# Display_Board_v4.net
KiCad netlist of a schematic drawn in EAGLE
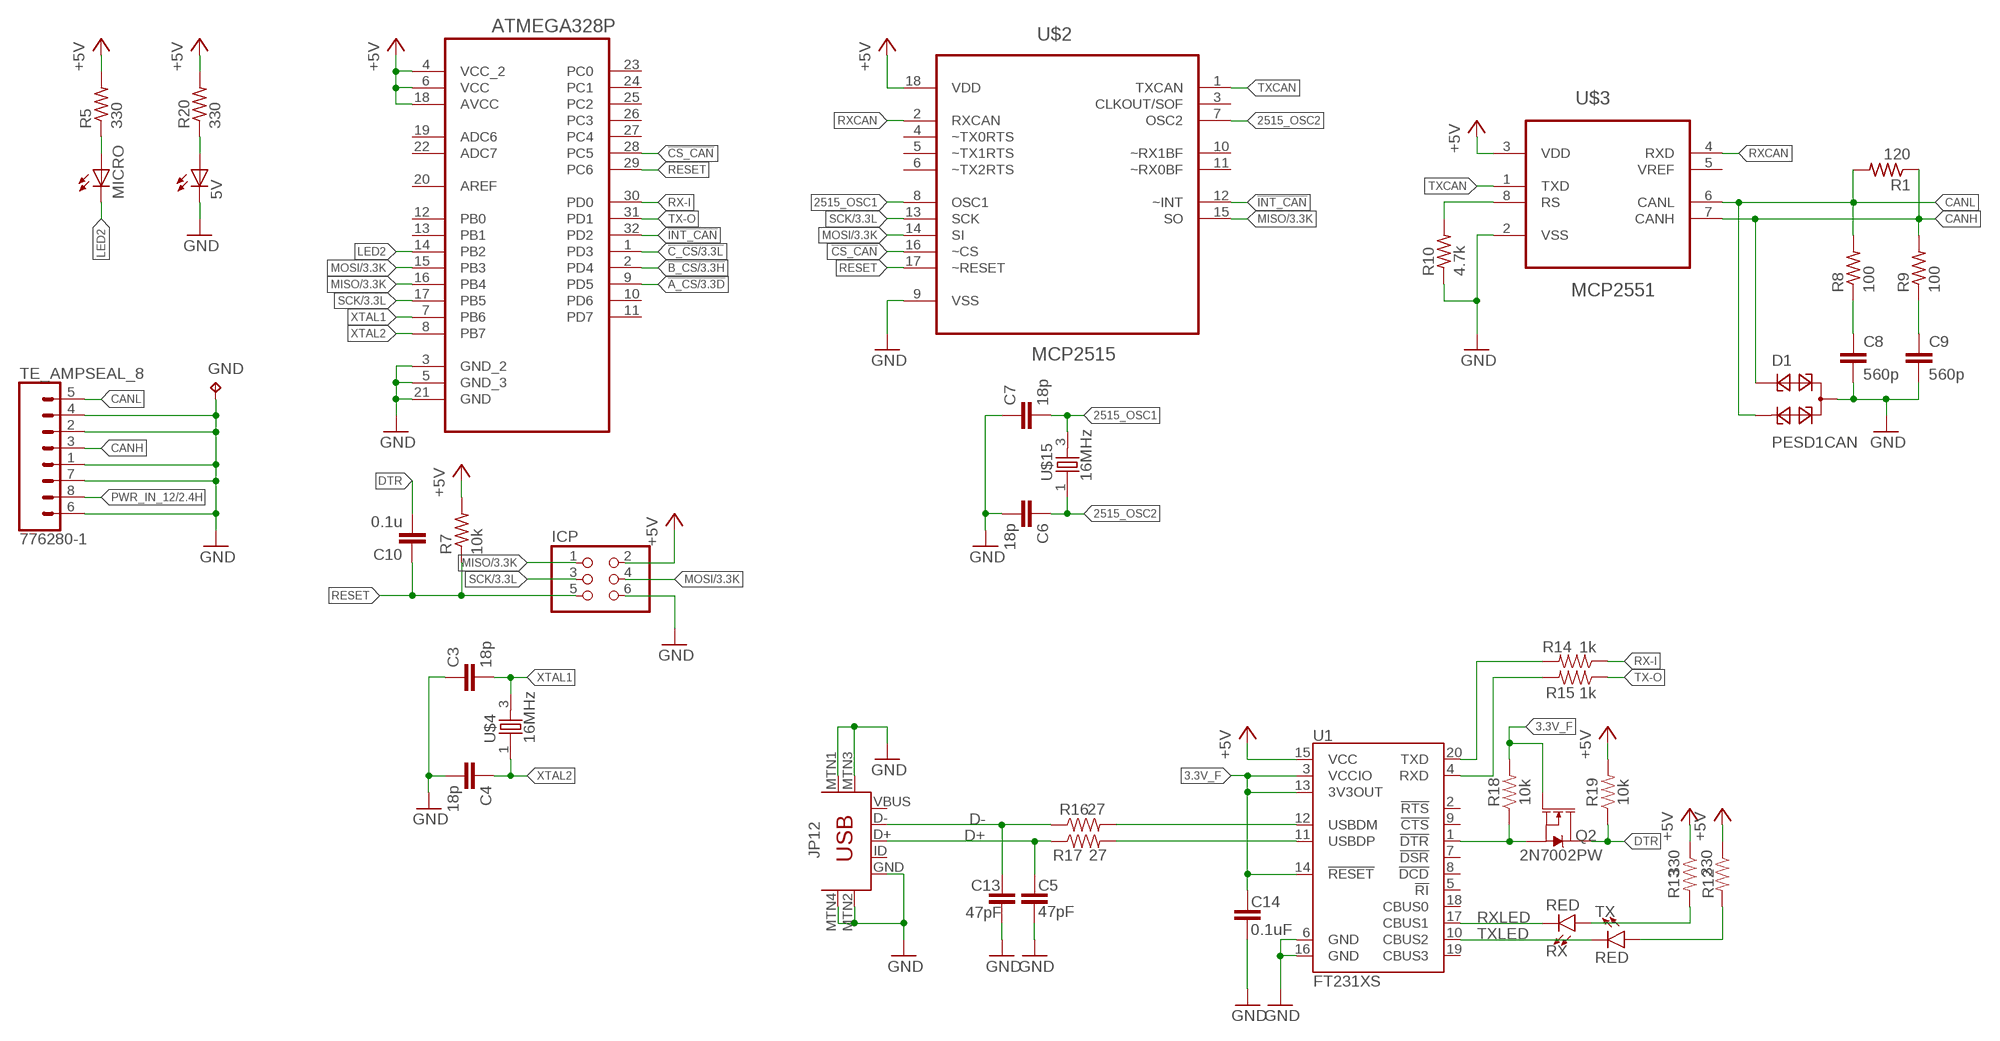
[diagram p0: schematic, sheet 1]
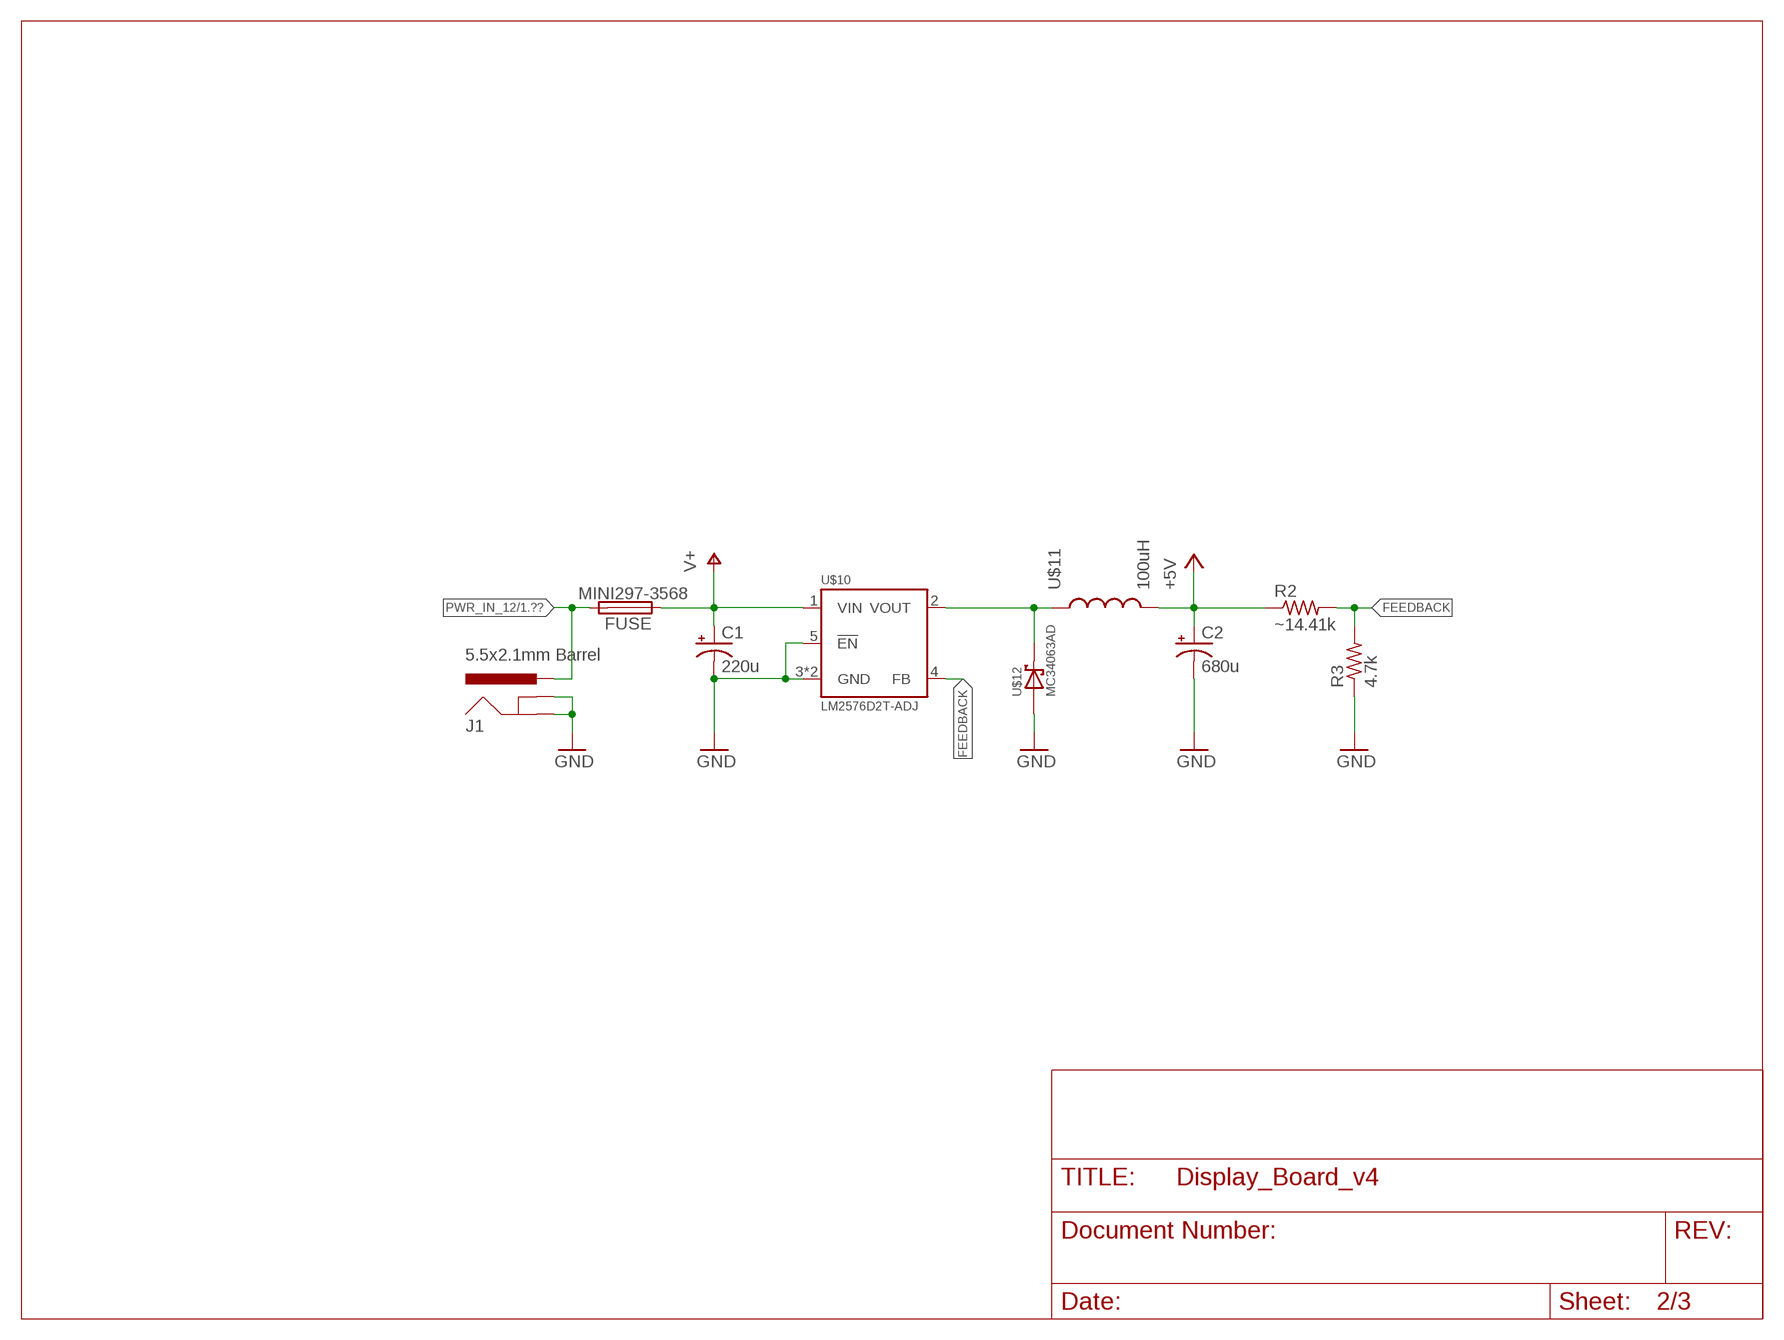
[diagram p1: schematic, sheet 2]
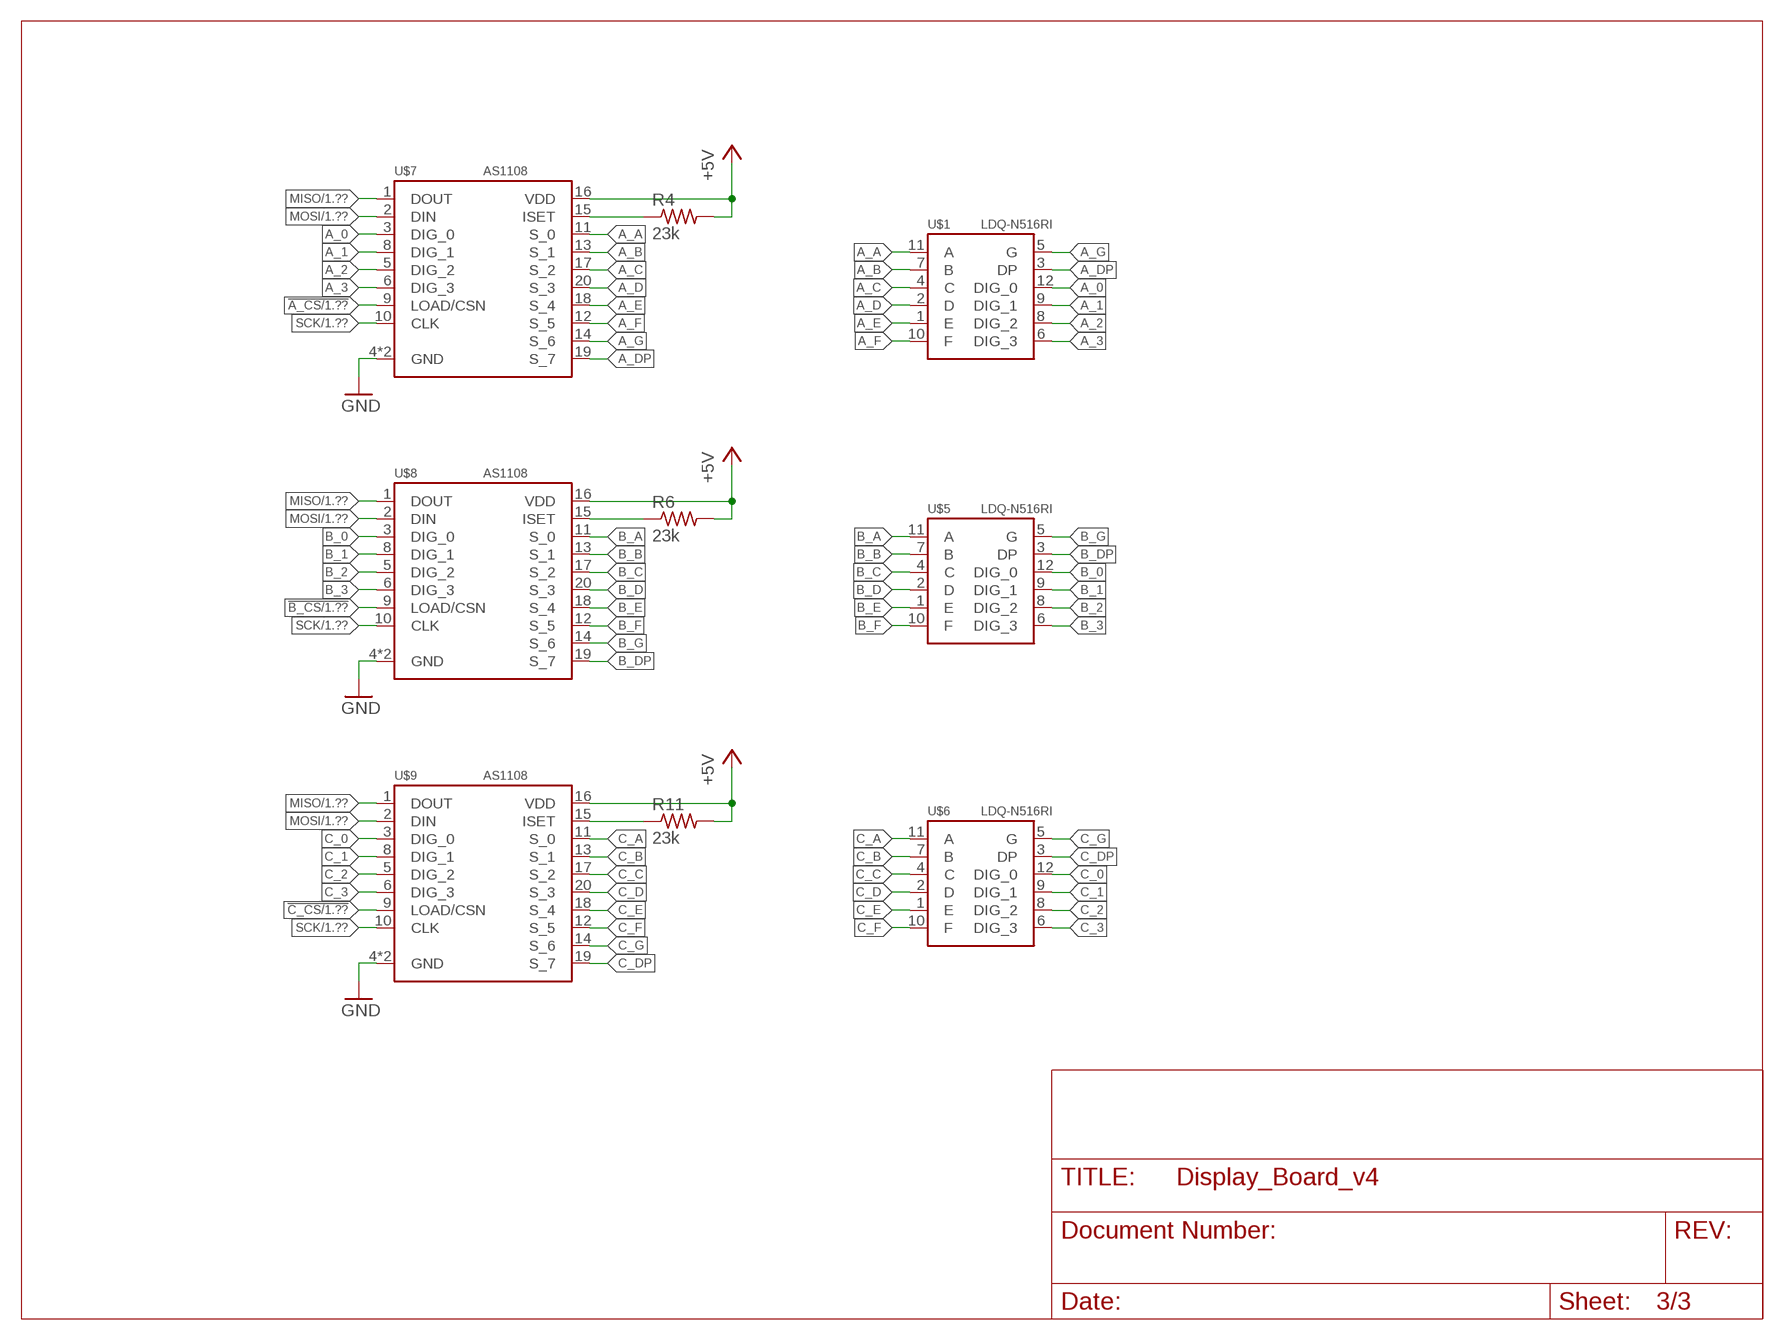
[diagram p2: schematic, sheet 3]

(export (version "E")
  (design (tool "Eeschema 10.0.6"))
  (components
    (comp (ref "5V")
      (value "LEDCHIP-LED0805")
      (footprint "eagle-import:CHIP-LED0805")
      (libsource (lib "eagle-import") (part "LEDCHIP-LED0805"))
    )
    (comp (ref "ATMEGA328P")
      (value "ATMEGA328P-AU")
      (footprint "eagle-import:QFP80P900X900X120-32N")
      (libsource (lib "eagle-import") (part "ATMEGA328P-AU"))
    )
    (comp (ref "C3")
      (value "18p")
      (footprint "eagle-import:C0805K")
      (libsource (lib "eagle-import") (part "resistor_C-EUC0805K"))
    )
    (comp (ref "C4")
      (value "18p")
      (footprint "eagle-import:C0805K")
      (libsource (lib "eagle-import") (part "resistor_C-EUC0805K"))
    )
    (comp (ref "C5")
      (value "47pF")
      (footprint "eagle-import:0603")
      (libsource (lib "eagle-import") (part "47PF-0603-50V-5%"))
    )
    (comp (ref "C6")
      (value "18p")
      (footprint "eagle-import:C0805K")
      (libsource (lib "eagle-import") (part "resistor_C-EUC0805K"))
    )
    (comp (ref "C7")
      (value "18p")
      (footprint "eagle-import:C0805K")
      (libsource (lib "eagle-import") (part "resistor_C-EUC0805K"))
    )
    (comp (ref "C8")
      (value "560p")
      (footprint "eagle-import:C0805K")
      (libsource (lib "eagle-import") (part "C-EUC0805K"))
    )
    (comp (ref "C9")
      (value "560p")
      (footprint "eagle-import:C0805K")
      (libsource (lib "eagle-import") (part "C-EUC0805K"))
    )
    (comp (ref "C10")
      (value "0.1u")
      (footprint "eagle-import:C0805K")
      (libsource (lib "eagle-import") (part "resistor_C-EUC0805K"))
    )
    (comp (ref "C13")
      (value "47pF")
      (footprint "eagle-import:0603")
      (libsource (lib "eagle-import") (part "47PF-0603-50V-5%"))
    )
    (comp (ref "C14")
      (value "0.1uF")
      (footprint "eagle-import:0603")
      (libsource (lib "eagle-import") (part "0.1UF-0603-25V-(+80/-20%)"))
    )
    (comp (ref "D1")
      (value "PESD1CAN")
      (footprint "eagle-import:SOT23")
      (libsource (lib "eagle-import") (part "PESD1CAN"))
    )
    (comp (ref "GND")
      (value "TPTP12SQ")
      (footprint "eagle-import:TP12SQ")
      (libsource (lib "eagle-import") (part "TPTP12SQ"))
    )
    (comp (ref "ICP")
      (value "PINHD-2X3")
      (footprint "eagle-import:2X03")
      (libsource (lib "eagle-import") (part "PINHD-2X3"))
    )
    (comp (ref "JP12")
      (value "USB-MINIB-5PIN")
      (footprint "eagle-import:USB-MINIB")
      (libsource (lib "eagle-import") (part "USB-MINIB-5PIN"))
    )
    (comp (ref "MICRO")
      (value "LEDCHIP-LED0805")
      (footprint "eagle-import:CHIP-LED0805")
      (libsource (lib "eagle-import") (part "LEDCHIP-LED0805"))
    )
    (comp (ref "Q2")
      (value "2N7002PW")
      (footprint "eagle-import:SOT323")
      (libsource (lib "eagle-import") (part "MOSFET-NCH-2N7002PW"))
    )
    (comp (ref "R1")
      (value "120")
      (footprint "eagle-import:R0805")
      (libsource (lib "eagle-import") (part "R-US_R0805"))
    )
    (comp (ref "R5")
      (value "330")
      (footprint "eagle-import:R0805")
      (libsource (lib "eagle-import") (part "resistor_R-US_R0805"))
    )
    (comp (ref "R7")
      (value "10k")
      (footprint "eagle-import:R0805")
      (libsource (lib "eagle-import") (part "R-US_R0805"))
    )
    (comp (ref "R8")
      (value "100")
      (footprint "eagle-import:R0805")
      (libsource (lib "eagle-import") (part "R-US_R0805"))
    )
    (comp (ref "R9")
      (value "100")
      (footprint "eagle-import:R0805")
      (libsource (lib "eagle-import") (part "R-US_R0805"))
    )
    (comp (ref "R10")
      (value "4.7k")
      (footprint "eagle-import:R0805")
      (libsource (lib "eagle-import") (part "R-US_R0805"))
    )
    (comp (ref "R12")
      (value "330")
      (footprint "eagle-import:0603")
      (libsource (lib "eagle-import") (part "1KOHM-0603-1/10W-1%"))
    )
    (comp (ref "R13")
      (value "330")
      (footprint "eagle-import:0603")
      (libsource (lib "eagle-import") (part "1KOHM-0603-1/10W-1%"))
    )
    (comp (ref "R14")
      (value "1k")
      (footprint "eagle-import:0603")
      (libsource (lib "eagle-import") (part "1KOHM-0603-1/10W-1%"))
    )
    (comp (ref "R15")
      (value "1k")
      (footprint "eagle-import:0603")
      (libsource (lib "eagle-import") (part "1KOHM-0603-1/10W-1%"))
    )
    (comp (ref "R16")
      (value "27")
      (footprint "eagle-import:0603")
      (libsource (lib "eagle-import") (part "27OHM-0603-1/10W-1%"))
    )
    (comp (ref "R17")
      (value "27")
      (footprint "eagle-import:0603")
      (libsource (lib "eagle-import") (part "27OHM-0603-1/10W-1%"))
    )
    (comp (ref "R18")
      (value "10k")
      (footprint "eagle-import:0603")
      (libsource (lib "eagle-import") (part "10KOHM-0603-1/10W-1%"))
    )
    (comp (ref "R19")
      (value "10k")
      (footprint "eagle-import:0603")
      (libsource (lib "eagle-import") (part "10KOHM-0603-1/10W-1%"))
    )
    (comp (ref "R20")
      (value "330")
      (footprint "eagle-import:R0805")
      (libsource (lib "eagle-import") (part "resistor_R-US_R0805"))
    )
    (comp (ref "RX")
      (value "RED")
      (footprint "eagle-import:LED-1206")
      (libsource (lib "eagle-import") (part "LED1206"))
    )
    (comp (ref "TE_AMPSEAL_8")
      (value "776280-1")
      (footprint "eagle-import:776280-1")
      (libsource (lib "eagle-import") (part "776280-1"))
    )
    (comp (ref "TX")
      (value "RED")
      (footprint "eagle-import:LED-1206")
      (libsource (lib "eagle-import") (part "LED1206"))
    )
    (comp (ref "U$2")
      (value "MCP2515")
      (footprint "eagle-import:SOIC127P1034X264-18N")
      (fields (field (name "MPN") "MCP2515-I/SO"))
      (libsource (lib "eagle-import") (part "MCP2515-I/SO"))
    )
    (comp (ref "U$3")
      (value "MCP2551")
      (footprint "eagle-import:SOIC127P600X175-8N")
      (fields (field (name "MPN") "MCP2551-I/SN"))
      (libsource (lib "eagle-import") (part "MCP2551-I/SN"))
    )
    (comp (ref "U$4")
      (value "16MHz")
      (footprint "eagle-import:CTS406")
      (libsource (lib "eagle-import") (part "406CYRYSTAL"))
    )
    (comp (ref "U$15")
      (value "16MHz")
      (footprint "eagle-import:CTS406")
      (libsource (lib "eagle-import") (part "406CYRYSTAL"))
    )
    (comp (ref "U1")
      (value "FT231XS")
      (footprint "eagle-import:SSOP20_L")
      (libsource (lib "eagle-import") (part "FT231XS"))
    )
    (comp (ref "R4")
      (value "23k")
      (footprint "eagle-import:R0603")
      (libsource (lib "eagle-import") (part "rcl_334_R-US_R0603"))
    )
    (comp (ref "R6")
      (value "23k")
      (footprint "eagle-import:R0603")
      (libsource (lib "eagle-import") (part "rcl_334_R-US_R0603"))
    )
    (comp (ref "R11")
      (value "23k")
      (footprint "eagle-import:R0603")
      (libsource (lib "eagle-import") (part "rcl_334_R-US_R0603"))
    )
    (comp (ref "U$1")
      (value "LDQ-N516RI")
      (footprint "eagle-import:4_DIGIT_7_SEGMENT_DISPLAY_0.56_")
      (libsource (lib "eagle-import") (part "LDQ-N516RI"))
    )
    (comp (ref "U$5")
      (value "LDQ-N516RI")
      (footprint "eagle-import:4_DIGIT_7_SEGMENT_DISPLAY_0.56_")
      (libsource (lib "eagle-import") (part "LDQ-N516RI"))
    )
    (comp (ref "U$6")
      (value "LDQ-N516RI")
      (footprint "eagle-import:4_DIGIT_7_SEGMENT_DISPLAY_0.56_")
      (libsource (lib "eagle-import") (part "LDQ-N516RI"))
    )
    (comp (ref "U$7")
      (value "AS1108")
      (footprint "eagle-import:SO20L")
      (libsource (lib "eagle-import") (part "AS1108"))
    )
    (comp (ref "U$8")
      (value "AS1108")
      (footprint "eagle-import:SO20L")
      (libsource (lib "eagle-import") (part "AS1108"))
    )
    (comp (ref "U$9")
      (value "AS1108")
      (footprint "eagle-import:SO20L")
      (libsource (lib "eagle-import") (part "AS1108"))
    )
    (comp (ref "C1")
      (value "220u")
      (footprint "eagle-import:UD-6,3X7,7_NICHICON")
      (libsource (lib "eagle-import") (part "CPOL-USUD-6,3X7,7"))
    )
    (comp (ref "C2")
      (value "680u")
      (footprint "eagle-import:UD-6,3X7,7_NICHICON")
      (libsource (lib "eagle-import") (part "CPOL-USUD-6,3X7,7"))
    )
    (comp (ref "FUSE")
      (value "MINI297-3568")
      (footprint "eagle-import:3568")
      (libsource (lib "eagle-import") (part "MINI297-3568"))
    )
    (comp (ref "J1")
      (value "5.5x2.1mm Barrel")
      (footprint "eagle-import:POWER_JACK_SMD")
      (libsource (lib "eagle-import") (part "POWER_JACKSMD"))
    )
    (comp (ref "R2")
      (value "~14.41k")
      (footprint "eagle-import:R0603")
      (libsource (lib "eagle-import") (part "rcl_334_R-US_R0603"))
    )
    (comp (ref "R3")
      (value "4.7k")
      (footprint "eagle-import:R0603")
      (libsource (lib "eagle-import") (part "rcl_334_R-US_R0603"))
    )
    (comp (ref "U$10")
      (value "LM2576D2T-ADJ")
      (footprint "eagle-import:TO263-5")
      (libsource (lib "eagle-import") (part "LM2576D2T-ADJ"))
    )
    (comp (ref "U$11")
      (value "100uH")
      (footprint "eagle-import:12MM_12MM_INDUCTOR")
      (libsource (lib "eagle-import") (part "INDUCTOR"))
    )
    (comp (ref "U$12")
      (value "MC34063AD")
      (footprint "eagle-import:SMC")
      (libsource (lib "eagle-import") (part "MC34063AD"))
    )
  )
  (nets
    (net (code "1") (name "+5V") (class "Default")
      (node (ref "ATMEGA328P") (pin "18") (pinfunction "AVCC_18") (pintype "power_in"))
      (node (ref "ATMEGA328P") (pin "4") (pinfunction "VCC_2_4") (pintype "power_in"))
      (node (ref "ATMEGA328P") (pin "6") (pinfunction "VCC_6") (pintype "power_in"))
      (node (ref "C2") (pin "+") (pinfunction "+_+") (pintype "passive"))
      (node (ref "ICP") (pin "2") (pinfunction "2_2") (pintype "passive"))
      (node (ref "R11") (pin "2") (pinfunction "2_2") (pintype "passive"))
      (node (ref "R12") (pin "1") (pinfunction "1_1") (pintype "passive"))
      (node (ref "R13") (pin "1") (pinfunction "1_1") (pintype "passive"))
      (node (ref "R19") (pin "2") (pinfunction "2_2") (pintype "passive"))
      (node (ref "R2") (pin "1") (pinfunction "1_1") (pintype "passive"))
      (node (ref "R20") (pin "2") (pinfunction "2_2") (pintype "passive"))
      (node (ref "R4") (pin "2") (pinfunction "2_2") (pintype "passive"))
      (node (ref "R5") (pin "2") (pinfunction "2_2") (pintype "passive"))
      (node (ref "R6") (pin "2") (pinfunction "2_2") (pintype "passive"))
      (node (ref "R7") (pin "2") (pinfunction "2_2") (pintype "passive"))
      (node (ref "U$11") (pin "P$2") (pinfunction "2_P$2") (pintype "passive"))
      (node (ref "U$2") (pin "18") (pinfunction "VDD_18") (pintype "power_in"))
      (node (ref "U$3") (pin "3") (pinfunction "VDD_3") (pintype "power_in"))
      (node (ref "U$7") (pin "16") (pinfunction "VDD_16") (pintype "bidirectional"))
      (node (ref "U$8") (pin "16") (pinfunction "VDD_16") (pintype "bidirectional"))
      (node (ref "U$9") (pin "16") (pinfunction "VDD_16") (pintype "bidirectional"))
      (node (ref "U1") (pin "15") (pinfunction "VCC_15") (pintype "bidirectional"))
    )
    (net (code "2") (name "3.3V_F") (class "Default")
      (node (ref "C14") (pin "1") (pinfunction "1_1") (pintype "passive"))
      (node (ref "Q2") (pin "1") (pinfunction "G_1") (pintype "bidirectional"))
      (node (ref "R18") (pin "2") (pinfunction "2_2") (pintype "passive"))
      (node (ref "U1") (pin "13") (pinfunction "3V3OUT_13") (pintype "bidirectional"))
      (node (ref "U1") (pin "14") (pinfunction "~{RESET}_14") (pintype "bidirectional"))
      (node (ref "U1") (pin "3") (pinfunction "VCCIO_3") (pintype "bidirectional"))
    )
    (net (code "3") (name "2515_OSC1") (class "Default")
      (node (ref "C7") (pin "2") (pinfunction "2_2") (pintype "passive"))
      (node (ref "U$15") (pin "3") (pinfunction "2_3") (pintype "passive"))
      (node (ref "U$2") (pin "8") (pinfunction "OSC1_8") (pintype "input"))
    )
    (net (code "4") (name "2515_OSC2") (class "Default")
      (node (ref "C6") (pin "1") (pinfunction "1_1") (pintype "passive"))
      (node (ref "U$15") (pin "1") (pinfunction "1_1") (pintype "passive"))
      (node (ref "U$2") (pin "7") (pinfunction "OSC2_7") (pintype "output"))
    )
    (net (code "5") (name "A_0") (class "Default")
      (node (ref "U$1") (pin "12") (pinfunction "DIG_0_12") (pintype "bidirectional"))
      (node (ref "U$7") (pin "3") (pinfunction "DIG_0_3") (pintype "bidirectional"))
    )
    (net (code "6") (name "A_1") (class "Default")
      (node (ref "U$1") (pin "9") (pinfunction "DIG_1_9") (pintype "bidirectional"))
      (node (ref "U$7") (pin "8") (pinfunction "DIG_1_8") (pintype "bidirectional"))
    )
    (net (code "7") (name "A_2") (class "Default")
      (node (ref "U$1") (pin "8") (pinfunction "DIG_2_8") (pintype "bidirectional"))
      (node (ref "U$7") (pin "5") (pinfunction "DIG_2_5") (pintype "bidirectional"))
    )
    (net (code "8") (name "A_3") (class "Default")
      (node (ref "U$1") (pin "6") (pinfunction "DIG_3_6") (pintype "bidirectional"))
      (node (ref "U$7") (pin "6") (pinfunction "DIG_3_6") (pintype "bidirectional"))
    )
    (net (code "9") (name "A_A") (class "Default")
      (node (ref "U$1") (pin "11") (pinfunction "A_11") (pintype "bidirectional"))
      (node (ref "U$7") (pin "11") (pinfunction "S_0_11") (pintype "bidirectional"))
    )
    (net (code "10") (name "A_B") (class "Default")
      (node (ref "U$1") (pin "7") (pinfunction "B_7") (pintype "bidirectional"))
      (node (ref "U$7") (pin "13") (pinfunction "S_1_13") (pintype "bidirectional"))
    )
    (net (code "11") (name "A_C") (class "Default")
      (node (ref "U$1") (pin "4") (pinfunction "C_4") (pintype "bidirectional"))
      (node (ref "U$7") (pin "17") (pinfunction "S_2_17") (pintype "bidirectional"))
    )
    (net (code "12") (name "A_D") (class "Default")
      (node (ref "U$1") (pin "2") (pinfunction "D_2") (pintype "bidirectional"))
      (node (ref "U$7") (pin "20") (pinfunction "S_3_20") (pintype "bidirectional"))
    )
    (net (code "13") (name "A_DP") (class "Default")
      (node (ref "U$1") (pin "3") (pinfunction "DP_3") (pintype "bidirectional"))
      (node (ref "U$7") (pin "19") (pinfunction "S_7_19") (pintype "bidirectional"))
    )
    (net (code "14") (name "A_E") (class "Default")
      (node (ref "U$1") (pin "1") (pinfunction "E_1") (pintype "bidirectional"))
      (node (ref "U$7") (pin "18") (pinfunction "S_4_18") (pintype "bidirectional"))
    )
    (net (code "15") (name "A_F") (class "Default")
      (node (ref "U$1") (pin "10") (pinfunction "F_10") (pintype "bidirectional"))
      (node (ref "U$7") (pin "12") (pinfunction "S_5_12") (pintype "bidirectional"))
    )
    (net (code "16") (name "A_G") (class "Default")
      (node (ref "U$1") (pin "5") (pinfunction "G_5") (pintype "bidirectional"))
      (node (ref "U$7") (pin "14") (pinfunction "S_6_14") (pintype "bidirectional"))
    )
    (net (code "17") (name "B_0") (class "Default")
      (node (ref "U$5") (pin "12") (pinfunction "DIG_0_12") (pintype "bidirectional"))
      (node (ref "U$8") (pin "3") (pinfunction "DIG_0_3") (pintype "bidirectional"))
    )
    (net (code "18") (name "B_1") (class "Default")
      (node (ref "U$5") (pin "9") (pinfunction "DIG_1_9") (pintype "bidirectional"))
      (node (ref "U$8") (pin "8") (pinfunction "DIG_1_8") (pintype "bidirectional"))
    )
    (net (code "19") (name "B_2") (class "Default")
      (node (ref "U$5") (pin "8") (pinfunction "DIG_2_8") (pintype "bidirectional"))
      (node (ref "U$8") (pin "5") (pinfunction "DIG_2_5") (pintype "bidirectional"))
    )
    (net (code "20") (name "B_3") (class "Default")
      (node (ref "U$5") (pin "6") (pinfunction "DIG_3_6") (pintype "bidirectional"))
      (node (ref "U$8") (pin "6") (pinfunction "DIG_3_6") (pintype "bidirectional"))
    )
    (net (code "21") (name "B_A") (class "Default")
      (node (ref "U$5") (pin "11") (pinfunction "A_11") (pintype "bidirectional"))
      (node (ref "U$8") (pin "11") (pinfunction "S_0_11") (pintype "bidirectional"))
    )
    (net (code "22") (name "B_B") (class "Default")
      (node (ref "U$5") (pin "7") (pinfunction "B_7") (pintype "bidirectional"))
      (node (ref "U$8") (pin "13") (pinfunction "S_1_13") (pintype "bidirectional"))
    )
    (net (code "23") (name "B_C") (class "Default")
      (node (ref "U$5") (pin "4") (pinfunction "C_4") (pintype "bidirectional"))
      (node (ref "U$8") (pin "17") (pinfunction "S_2_17") (pintype "bidirectional"))
    )
    (net (code "24") (name "B_D") (class "Default")
      (node (ref "U$5") (pin "2") (pinfunction "D_2") (pintype "bidirectional"))
      (node (ref "U$8") (pin "20") (pinfunction "S_3_20") (pintype "bidirectional"))
    )
    (net (code "25") (name "B_DP") (class "Default")
      (node (ref "U$5") (pin "3") (pinfunction "DP_3") (pintype "bidirectional"))
      (node (ref "U$8") (pin "19") (pinfunction "S_7_19") (pintype "bidirectional"))
    )
    (net (code "26") (name "B_E") (class "Default")
      (node (ref "U$5") (pin "1") (pinfunction "E_1") (pintype "bidirectional"))
      (node (ref "U$8") (pin "18") (pinfunction "S_4_18") (pintype "bidirectional"))
    )
    (net (code "27") (name "B_F") (class "Default")
      (node (ref "U$5") (pin "10") (pinfunction "F_10") (pintype "bidirectional"))
      (node (ref "U$8") (pin "12") (pinfunction "S_5_12") (pintype "bidirectional"))
    )
    (net (code "28") (name "B_G") (class "Default")
      (node (ref "U$5") (pin "5") (pinfunction "G_5") (pintype "bidirectional"))
      (node (ref "U$8") (pin "14") (pinfunction "S_6_14") (pintype "bidirectional"))
    )
    (net (code "29") (name "CANH") (class "Default")
      (node (ref "D1") (pin "1") (pinfunction "1_1") (pintype "passive"))
      (node (ref "R1") (pin "1") (pinfunction "1_1") (pintype "passive"))
      (node (ref "R9") (pin "2") (pinfunction "2_2") (pintype "passive"))
      (node (ref "TE_AMPSEAL_8") (pin "3") (pinfunction "5_3") (pintype "passive"))
      (node (ref "U$3") (pin "7") (pinfunction "CANH_7") (pintype "bidirectional"))
    )
    (net (code "30") (name "CANL") (class "Default")
      (node (ref "D1") (pin "2") (pinfunction "2_2") (pintype "passive"))
      (node (ref "R1") (pin "2") (pinfunction "2_2") (pintype "passive"))
      (node (ref "R8") (pin "2") (pinfunction "2_2") (pintype "passive"))
      (node (ref "TE_AMPSEAL_8") (pin "5") (pinfunction "8_5") (pintype "passive"))
      (node (ref "U$3") (pin "6") (pinfunction "CANL_6") (pintype "bidirectional"))
    )
    (net (code "31") (name "C_0") (class "Default")
      (node (ref "U$6") (pin "12") (pinfunction "DIG_0_12") (pintype "bidirectional"))
      (node (ref "U$9") (pin "3") (pinfunction "DIG_0_3") (pintype "bidirectional"))
    )
    (net (code "32") (name "C_1") (class "Default")
      (node (ref "U$6") (pin "9") (pinfunction "DIG_1_9") (pintype "bidirectional"))
      (node (ref "U$9") (pin "8") (pinfunction "DIG_1_8") (pintype "bidirectional"))
    )
    (net (code "33") (name "C_2") (class "Default")
      (node (ref "U$6") (pin "8") (pinfunction "DIG_2_8") (pintype "bidirectional"))
      (node (ref "U$9") (pin "5") (pinfunction "DIG_2_5") (pintype "bidirectional"))
    )
    (net (code "34") (name "C_3") (class "Default")
      (node (ref "U$6") (pin "6") (pinfunction "DIG_3_6") (pintype "bidirectional"))
      (node (ref "U$9") (pin "6") (pinfunction "DIG_3_6") (pintype "bidirectional"))
    )
    (net (code "35") (name "C_A") (class "Default")
      (node (ref "U$6") (pin "11") (pinfunction "A_11") (pintype "bidirectional"))
      (node (ref "U$9") (pin "11") (pinfunction "S_0_11") (pintype "bidirectional"))
    )
    (net (code "36") (name "C_B") (class "Default")
      (node (ref "U$6") (pin "7") (pinfunction "B_7") (pintype "bidirectional"))
      (node (ref "U$9") (pin "13") (pinfunction "S_1_13") (pintype "bidirectional"))
    )
    (net (code "37") (name "C_C") (class "Default")
      (node (ref "U$6") (pin "4") (pinfunction "C_4") (pintype "bidirectional"))
      (node (ref "U$9") (pin "17") (pinfunction "S_2_17") (pintype "bidirectional"))
    )
    (net (code "38") (name "C_D") (class "Default")
      (node (ref "U$6") (pin "2") (pinfunction "D_2") (pintype "bidirectional"))
      (node (ref "U$9") (pin "20") (pinfunction "S_3_20") (pintype "bidirectional"))
    )
    (net (code "39") (name "C_DP") (class "Default")
      (node (ref "U$6") (pin "3") (pinfunction "DP_3") (pintype "bidirectional"))
      (node (ref "U$9") (pin "19") (pinfunction "S_7_19") (pintype "bidirectional"))
    )
    (net (code "40") (name "C_E") (class "Default")
      (node (ref "U$6") (pin "1") (pinfunction "E_1") (pintype "bidirectional"))
      (node (ref "U$9") (pin "18") (pinfunction "S_4_18") (pintype "bidirectional"))
    )
    (net (code "41") (name "C_F") (class "Default")
      (node (ref "U$6") (pin "10") (pinfunction "F_10") (pintype "bidirectional"))
      (node (ref "U$9") (pin "12") (pinfunction "S_5_12") (pintype "bidirectional"))
    )
    (net (code "42") (name "C_G") (class "Default")
      (node (ref "U$6") (pin "5") (pinfunction "G_5") (pintype "bidirectional"))
      (node (ref "U$9") (pin "14") (pinfunction "S_6_14") (pintype "bidirectional"))
    )
    (net (code "43") (name "D+") (class "Default")
      (node (ref "C5") (pin "1") (pinfunction "1_1") (pintype "passive"))
      (node (ref "JP12") (pin "D+") (pinfunction "D+_D+") (pintype "bidirectional"))
      (node (ref "R17") (pin "1") (pinfunction "1_1") (pintype "passive"))
    )
    (net (code "44") (name "D-") (class "Default")
      (node (ref "C13") (pin "1") (pinfunction "1_1") (pintype "passive"))
      (node (ref "JP12") (pin "D-") (pinfunction "D-_D-") (pintype "bidirectional"))
      (node (ref "R16") (pin "1") (pinfunction "1_1") (pintype "passive"))
    )
    (net (code "45") (name "DTR") (class "Default")
      (node (ref "C10") (pin "2") (pinfunction "2_2") (pintype "passive"))
      (node (ref "Q2") (pin "3") (pinfunction "D_3") (pintype "bidirectional"))
      (node (ref "R19") (pin "1") (pinfunction "1_1") (pintype "passive"))
    )
    (net (code "46") (name "FEEDBACK") (class "Default")
      (node (ref "R2") (pin "2") (pinfunction "2_2") (pintype "passive"))
      (node (ref "R3") (pin "2") (pinfunction "2_2") (pintype "passive"))
      (node (ref "U$10") (pin "4") (pinfunction "FB_4") (pintype "input"))
    )
    (net (code "47") (name "GND") (class "Default")
      (node (ref "5V") (pin "C") (pinfunction "C_C") (pintype "passive"))
      (node (ref "ATMEGA328P") (pin "21") (pinfunction "GND_21") (pintype "passive"))
      (node (ref "ATMEGA328P") (pin "3") (pinfunction "GND_2_3") (pintype "passive"))
      (node (ref "ATMEGA328P") (pin "5") (pinfunction "GND_3_5") (pintype "passive"))
      (node (ref "C1") (pin "-") (pinfunction "-_-") (pintype "passive"))
      (node (ref "C13") (pin "2") (pinfunction "2_2") (pintype "passive"))
      (node (ref "C14") (pin "2") (pinfunction "2_2") (pintype "passive"))
      (node (ref "C2") (pin "-") (pinfunction "-_-") (pintype "passive"))
      (node (ref "C3") (pin "1") (pinfunction "1_1") (pintype "passive"))
      (node (ref "C4") (pin "2") (pinfunction "2_2") (pintype "passive"))
      (node (ref "C5") (pin "2") (pinfunction "2_2") (pintype "passive"))
      (node (ref "C6") (pin "2") (pinfunction "2_2") (pintype "passive"))
      (node (ref "C7") (pin "1") (pinfunction "1_1") (pintype "passive"))
      (node (ref "C8") (pin "2") (pinfunction "2_2") (pintype "passive"))
      (node (ref "C9") (pin "2") (pinfunction "2_2") (pintype "passive"))
      (node (ref "D1") (pin "3") (pinfunction "3_3") (pintype "passive"))
      (node (ref "GND") (pin "TP") (pinfunction "TP_TP") (pintype "input"))
      (node (ref "ICP") (pin "6") (pinfunction "6_6") (pintype "passive"))
      (node (ref "J1") (pin "GND") (pinfunction "GNDBREAK_GND") (pintype "bidirectional"))
      (node (ref "J1") (pin "P$4") (pinfunction "GND_P$4") (pintype "bidirectional"))
      (node (ref "JP12") (pin "GND") (pinfunction "GND_GND") (pintype "bidirectional"))
      (node (ref "JP12") (pin "MTN1") (pinfunction "MTN2_MTN1") (pintype "bidirectional"))
      (node (ref "JP12") (pin "MTN2") (pinfunction "MTN3_MTN2") (pintype "bidirectional"))
      (node (ref "JP12") (pin "MTN3") (pinfunction "MTN1_MTN3") (pintype "bidirectional"))
      (node (ref "JP12") (pin "MTN4") (pinfunction "MTN4_MTN4") (pintype "bidirectional"))
      (node (ref "R10") (pin "1") (pinfunction "1_1") (pintype "passive"))
      (node (ref "R3") (pin "1") (pinfunction "1_1") (pintype "passive"))
      (node (ref "TE_AMPSEAL_8") (pin "1") (pinfunction "4_1") (pintype "passive"))
      (node (ref "TE_AMPSEAL_8") (pin "2") (pinfunction "6_2") (pintype "passive"))
      (node (ref "TE_AMPSEAL_8") (pin "4") (pinfunction "7_4") (pintype "passive"))
      (node (ref "TE_AMPSEAL_8") (pin "6") (pinfunction "1_6") (pintype "passive"))
      (node (ref "TE_AMPSEAL_8") (pin "7") (pinfunction "3_7") (pintype "passive"))
      (node (ref "U$10") (pin "3") (pinfunction "GND_3") (pintype "power_in"))
      (node (ref "U$10") (pin "5") (pinfunction "~{EN}_5") (pintype "input"))
      (node (ref "U$10") (pin "6") (pinfunction "GND_6") (pintype "power_in"))
      (node (ref "U$12") (pin "A") (pinfunction "A_A") (pintype "bidirectional"))
      (node (ref "U$2") (pin "9") (pinfunction "VSS_9") (pintype "power_in"))
      (node (ref "U$3") (pin "2") (pinfunction "VSS_2") (pintype "passive"))
      (node (ref "U$7") (pin "4") (pinfunction "GND_4") (pintype "bidirectional"))
      (node (ref "U$7") (pin "7") (pinfunction "GND_7") (pintype "bidirectional"))
      (node (ref "U$8") (pin "4") (pinfunction "GND_4") (pintype "bidirectional"))
      (node (ref "U$8") (pin "7") (pinfunction "GND_7") (pintype "bidirectional"))
      (node (ref "U$9") (pin "4") (pinfunction "GND_4") (pintype "bidirectional"))
      (node (ref "U$9") (pin "7") (pinfunction "GND_7") (pintype "bidirectional"))
      (node (ref "U1") (pin "16") (pinfunction "GND_16") (pintype "bidirectional"))
      (node (ref "U1") (pin "6") (pinfunction "GND_6") (pintype "bidirectional"))
    )
    (net (code "48") (name "LED2") (class "Default")
      (node (ref "ATMEGA328P") (pin "14") (pinfunction "PB2_14") (pintype "bidirectional"))
      (node (ref "MICRO") (pin "C") (pinfunction "C_C") (pintype "passive"))
    )
    (net (code "49") (name "MISO") (class "Default")
      (node (ref "ATMEGA328P") (pin "16") (pinfunction "PB4_16") (pintype "bidirectional"))
      (node (ref "ICP") (pin "1") (pinfunction "1_1") (pintype "passive"))
      (node (ref "U$2") (pin "15") (pinfunction "SO_15") (pintype "output"))
      (node (ref "U$7") (pin "1") (pinfunction "DOUT_1") (pintype "bidirectional"))
      (node (ref "U$8") (pin "1") (pinfunction "DOUT_1") (pintype "bidirectional"))
      (node (ref "U$9") (pin "1") (pinfunction "DOUT_1") (pintype "bidirectional"))
    )
    (net (code "50") (name "MOSI") (class "Default")
      (node (ref "ATMEGA328P") (pin "15") (pinfunction "PB3_15") (pintype "bidirectional"))
      (node (ref "ICP") (pin "4") (pinfunction "4_4") (pintype "passive"))
      (node (ref "U$2") (pin "14") (pinfunction "SI_14") (pintype "input"))
      (node (ref "U$7") (pin "2") (pinfunction "DIN_2") (pintype "bidirectional"))
      (node (ref "U$8") (pin "2") (pinfunction "DIN_2") (pintype "bidirectional"))
      (node (ref "U$9") (pin "2") (pinfunction "DIN_2") (pintype "bidirectional"))
    )
    (net (code "51") (name "Net-(5V-PadA)") (class "Default")
      (node (ref "5V") (pin "A") (pinfunction "A_A") (pintype "passive"))
      (node (ref "R20") (pin "1") (pinfunction "1_1") (pintype "passive"))
    )
    (net (code "52") (name "Net-(C8-Pad1)") (class "Default")
      (node (ref "C8") (pin "1") (pinfunction "1_1") (pintype "passive"))
      (node (ref "R8") (pin "1") (pinfunction "1_1") (pintype "passive"))
    )
    (net (code "53") (name "Net-(C9-Pad1)") (class "Default")
      (node (ref "C9") (pin "1") (pinfunction "1_1") (pintype "passive"))
      (node (ref "R9") (pin "1") (pinfunction "1_1") (pintype "passive"))
    )
    (net (code "54") (name "Net-(MICRO-PadA)") (class "Default")
      (node (ref "MICRO") (pin "A") (pinfunction "A_A") (pintype "passive"))
      (node (ref "R5") (pin "1") (pinfunction "1_1") (pintype "passive"))
    )
    (net (code "55") (name "Net-(Q2-S)") (class "Default")
      (node (ref "Q2") (pin "2") (pinfunction "S_2") (pintype "bidirectional"))
      (node (ref "R18") (pin "1") (pinfunction "1_1") (pintype "passive"))
      (node (ref "U1") (pin "1") (pinfunction "~{DTR}_1") (pintype "bidirectional"))
    )
    (net (code "56") (name "Net-(R12-Pad2)") (class "Default")
      (node (ref "R12") (pin "2") (pinfunction "2_2") (pintype "passive"))
      (node (ref "TX") (pin "A") (pinfunction "A_A") (pintype "passive"))
    )
    (net (code "57") (name "Net-(R13-Pad2)") (class "Default")
      (node (ref "R13") (pin "2") (pinfunction "2_2") (pintype "passive"))
      (node (ref "RX") (pin "A") (pinfunction "A_A") (pintype "passive"))
    )
    (net (code "58") (name "Net-(U$3-RS)") (class "Default")
      (node (ref "R10") (pin "2") (pinfunction "2_2") (pintype "passive"))
      (node (ref "U$3") (pin "8") (pinfunction "RS_8") (pintype "input"))
    )
    (net (code "59") (name "Net-(U$7-ISET)") (class "Default")
      (node (ref "R4") (pin "1") (pinfunction "1_1") (pintype "passive"))
      (node (ref "U$7") (pin "15") (pinfunction "ISET_15") (pintype "bidirectional"))
    )
    (net (code "60") (name "Net-(U$8-ISET)") (class "Default")
      (node (ref "R6") (pin "1") (pinfunction "1_1") (pintype "passive"))
      (node (ref "U$8") (pin "15") (pinfunction "ISET_15") (pintype "bidirectional"))
    )
    (net (code "61") (name "Net-(U$9-ISET)") (class "Default")
      (node (ref "R11") (pin "1") (pinfunction "1_1") (pintype "passive"))
      (node (ref "U$9") (pin "15") (pinfunction "ISET_15") (pintype "bidirectional"))
    )
    (net (code "62") (name "Net-(U$10-VOUT)") (class "Default")
      (node (ref "U$10") (pin "2") (pinfunction "VOUT_2") (pintype "output"))
      (node (ref "U$11") (pin "P$1") (pinfunction "1_P$1") (pintype "passive"))
      (node (ref "U$12") (pin "C") (pinfunction "C_C") (pintype "bidirectional"))
    )
    (net (code "63") (name "Net-(U1-RXD)") (class "Default")
      (node (ref "R15") (pin "2") (pinfunction "2_2") (pintype "passive"))
      (node (ref "U1") (pin "4") (pinfunction "RXD_4") (pintype "bidirectional"))
    )
    (net (code "64") (name "Net-(U1-TXD)") (class "Default")
      (node (ref "R14") (pin "2") (pinfunction "2_2") (pintype "passive"))
      (node (ref "U1") (pin "20") (pinfunction "TXD_20") (pintype "bidirectional"))
    )
    (net (code "65") (name "Net-(U1-USBDM)") (class "Default")
      (node (ref "R16") (pin "2") (pinfunction "2_2") (pintype "passive"))
      (node (ref "U1") (pin "12") (pinfunction "USBDM_12") (pintype "bidirectional"))
    )
    (net (code "66") (name "Net-(U1-USBDP)") (class "Default")
      (node (ref "R17") (pin "2") (pinfunction "2_2") (pintype "passive"))
      (node (ref "U1") (pin "11") (pinfunction "USBDP_11") (pintype "bidirectional"))
    )
    (net (code "67") (name "PWR_IN_12") (class "Default")
      (node (ref "FUSE") (pin "P$2") (pinfunction "2_P$2") (pintype "passive"))
      (node (ref "FUSE") (pin "P$3") (pinfunction "2_P$3") (pintype "passive"))
      (node (ref "J1") (pin "VIN0") (pinfunction "PWR_VIN0") (pintype "bidirectional"))
      (node (ref "TE_AMPSEAL_8") (pin "8") (pinfunction "2_8") (pintype "passive"))
    )
    (net (code "68") (name "RESET") (class "Default")
      (node (ref "ATMEGA328P") (pin "29") (pinfunction "PC6_29") (pintype "bidirectional"))
      (node (ref "C10") (pin "1") (pinfunction "1_1") (pintype "passive"))
      (node (ref "ICP") (pin "5") (pinfunction "5_5") (pintype "passive"))
      (node (ref "R7") (pin "1") (pinfunction "1_1") (pintype "passive"))
      (node (ref "U$2") (pin "17") (pinfunction "~{RESET}_17") (pintype "input"))
    )
    (net (code "69") (name "RX-I") (class "Default")
      (node (ref "ATMEGA328P") (pin "30") (pinfunction "PD0_30") (pintype "bidirectional"))
      (node (ref "R14") (pin "1") (pinfunction "1_1") (pintype "passive"))
    )
    (net (code "70") (name "RXCAN") (class "Default")
      (node (ref "U$2") (pin "2") (pinfunction "RXCAN_2") (pintype "input"))
      (node (ref "U$3") (pin "4") (pinfunction "RXD_4") (pintype "output"))
    )
    (net (code "71") (name "RXLED") (class "Default")
      (node (ref "RX") (pin "C") (pinfunction "C_C") (pintype "passive"))
      (node (ref "U1") (pin "17") (pinfunction "CBUS1_17") (pintype "bidirectional"))
    )
    (net (code "72") (name "SCK") (class "Default")
      (node (ref "ATMEGA328P") (pin "17") (pinfunction "PB5_17") (pintype "bidirectional"))
      (node (ref "ICP") (pin "3") (pinfunction "3_3") (pintype "passive"))
      (node (ref "U$2") (pin "13") (pinfunction "SCK_13") (pintype "input"))
      (node (ref "U$7") (pin "10") (pinfunction "CLK_10") (pintype "bidirectional"))
      (node (ref "U$8") (pin "10") (pinfunction "CLK_10") (pintype "bidirectional"))
      (node (ref "U$9") (pin "10") (pinfunction "CLK_10") (pintype "bidirectional"))
    )
    (net (code "73") (name "TX-O") (class "Default")
      (node (ref "ATMEGA328P") (pin "31") (pinfunction "PD1_31") (pintype "bidirectional"))
      (node (ref "R15") (pin "1") (pinfunction "1_1") (pintype "passive"))
    )
    (net (code "74") (name "TXCAN") (class "Default")
      (node (ref "U$2") (pin "1") (pinfunction "TXCAN_1") (pintype "output"))
      (node (ref "U$3") (pin "1") (pinfunction "TXD_1") (pintype "input"))
    )
    (net (code "75") (name "TXLED") (class "Default")
      (node (ref "TX") (pin "C") (pinfunction "C_C") (pintype "passive"))
      (node (ref "U1") (pin "10") (pinfunction "CBUS2_10") (pintype "bidirectional"))
    )
    (net (code "76") (name "V+") (class "Default")
      (node (ref "C1") (pin "+") (pinfunction "+_+") (pintype "passive"))
      (node (ref "FUSE") (pin "P$1") (pinfunction "1_P$1") (pintype "passive"))
      (node (ref "FUSE") (pin "P$4") (pinfunction "1_P$4") (pintype "passive"))
      (node (ref "U$10") (pin "1") (pinfunction "VIN_1") (pintype "power_in"))
    )
    (net (code "77") (name "XTAL1") (class "Default")
      (node (ref "ATMEGA328P") (pin "7") (pinfunction "PB6_7") (pintype "bidirectional"))
      (node (ref "C3") (pin "2") (pinfunction "2_2") (pintype "passive"))
      (node (ref "U$4") (pin "3") (pinfunction "2_3") (pintype "passive"))
    )
    (net (code "78") (name "XTAL2") (class "Default")
      (node (ref "ATMEGA328P") (pin "8") (pinfunction "PB7_8") (pintype "bidirectional"))
      (node (ref "C4") (pin "1") (pinfunction "1_1") (pintype "passive"))
      (node (ref "U$4") (pin "1") (pinfunction "1_1") (pintype "passive"))
    )
    (net (code "79") (name "unconnected-(ATMEGA328P-ADC6-Pad19)") (class "Default")
      (node (ref "ATMEGA328P") (pin "19") (pinfunction "ADC6_19") (pintype "input"))
    )
    (net (code "80") (name "unconnected-(ATMEGA328P-ADC7-Pad22)") (class "Default")
      (node (ref "ATMEGA328P") (pin "22") (pinfunction "ADC7_22") (pintype "input"))
    )
    (net (code "81") (name "unconnected-(ATMEGA328P-AREF-Pad20)") (class "Default")
      (node (ref "ATMEGA328P") (pin "20") (pinfunction "AREF_20") (pintype "input"))
    )
    (net (code "82") (name "unconnected-(ATMEGA328P-PB0-Pad12)") (class "Default")
      (node (ref "ATMEGA328P") (pin "12") (pinfunction "PB0_12") (pintype "bidirectional"))
    )
    (net (code "83") (name "unconnected-(ATMEGA328P-PB1-Pad13)") (class "Default")
      (node (ref "ATMEGA328P") (pin "13") (pinfunction "PB1_13") (pintype "bidirectional"))
    )
    (net (code "84") (name "unconnected-(ATMEGA328P-PC0-Pad23)") (class "Default")
      (node (ref "ATMEGA328P") (pin "23") (pinfunction "PC0_23") (pintype "bidirectional"))
    )
    (net (code "85") (name "unconnected-(ATMEGA328P-PC1-Pad24)") (class "Default")
      (node (ref "ATMEGA328P") (pin "24") (pinfunction "PC1_24") (pintype "bidirectional"))
    )
    (net (code "86") (name "unconnected-(ATMEGA328P-PC2-Pad25)") (class "Default")
      (node (ref "ATMEGA328P") (pin "25") (pinfunction "PC2_25") (pintype "bidirectional"))
    )
    (net (code "87") (name "unconnected-(ATMEGA328P-PC3-Pad26)") (class "Default")
      (node (ref "ATMEGA328P") (pin "26") (pinfunction "PC3_26") (pintype "bidirectional"))
    )
    (net (code "88") (name "unconnected-(ATMEGA328P-PC4-Pad27)") (class "Default")
      (node (ref "ATMEGA328P") (pin "27") (pinfunction "PC4_27") (pintype "bidirectional"))
    )
    (net (code "89") (name "unconnected-(ATMEGA328P-PD6-Pad10)") (class "Default")
      (node (ref "ATMEGA328P") (pin "10") (pinfunction "PD6_10") (pintype "bidirectional"))
    )
    (net (code "90") (name "unconnected-(ATMEGA328P-PD7-Pad11)") (class "Default")
      (node (ref "ATMEGA328P") (pin "11") (pinfunction "PD7_11") (pintype "bidirectional"))
    )
    (net (code "91") (name "unconnected-(JP12-PadID)") (class "Default")
      (node (ref "JP12") (pin "ID") (pinfunction "ID_ID") (pintype "bidirectional"))
    )
    (net (code "92") (name "unconnected-(JP12-PadVBUS)") (class "Default")
      (node (ref "JP12") (pin "VBUS") (pinfunction "VBUS_VBUS") (pintype "bidirectional"))
    )
    (net (code "93") (name "unconnected-(U$2-CLKOUT{slash}SOF-Pad3)") (class "Default")
      (node (ref "U$2") (pin "3") (pinfunction "CLKOUT/SOF_3") (pintype "output"))
    )
    (net (code "94") (name "unconnected-(U$2-~{RX0BF}-Pad11)") (class "Default")
      (node (ref "U$2") (pin "11") (pinfunction "~{RX0BF}_11") (pintype "output"))
    )
    (net (code "95") (name "unconnected-(U$2-~{RX1BF}-Pad10)") (class "Default")
      (node (ref "U$2") (pin "10") (pinfunction "~{RX1BF}_10") (pintype "output"))
    )
    (net (code "96") (name "unconnected-(U$2-~{TX0RTS}-Pad4)") (class "Default")
      (node (ref "U$2") (pin "4") (pinfunction "~{TX0RTS}_4") (pintype "input"))
    )
    (net (code "97") (name "unconnected-(U$2-~{TX1RTS}-Pad5)") (class "Default")
      (node (ref "U$2") (pin "5") (pinfunction "~{TX1RTS}_5") (pintype "input"))
    )
    (net (code "98") (name "unconnected-(U$2-~{TX2RTS}-Pad6)") (class "Default")
      (node (ref "U$2") (pin "6") (pinfunction "~{TX2RTS}_6") (pintype "input"))
    )
    (net (code "99") (name "unconnected-(U$3-VREF-Pad5)") (class "Default")
      (node (ref "U$3") (pin "5") (pinfunction "VREF_5") (pintype "output"))
    )
    (net (code "100") (name "unconnected-(U1-CBUS0-Pad18)") (class "Default")
      (node (ref "U1") (pin "18") (pinfunction "CBUS0_18") (pintype "bidirectional"))
    )
    (net (code "101") (name "unconnected-(U1-CBUS3-Pad19)") (class "Default")
      (node (ref "U1") (pin "19") (pinfunction "CBUS3_19") (pintype "bidirectional"))
    )
    (net (code "102") (name "unconnected-(U1-~{CTS}-Pad9)") (class "Default")
      (node (ref "U1") (pin "9") (pinfunction "~{CTS}_9") (pintype "bidirectional"))
    )
    (net (code "103") (name "unconnected-(U1-~{DCD}-Pad8)") (class "Default")
      (node (ref "U1") (pin "8") (pinfunction "~{DCD}_8") (pintype "bidirectional"))
    )
    (net (code "104") (name "unconnected-(U1-~{DSR}-Pad7)") (class "Default")
      (node (ref "U1") (pin "7") (pinfunction "~{DSR}_7") (pintype "bidirectional"))
    )
    (net (code "105") (name "unconnected-(U1-~{RI}-Pad5)") (class "Default")
      (node (ref "U1") (pin "5") (pinfunction "~{RI}_5") (pintype "bidirectional"))
    )
    (net (code "106") (name "unconnected-(U1-~{RTS}-Pad2)") (class "Default")
      (node (ref "U1") (pin "2") (pinfunction "~{RTS}_2") (pintype "bidirectional"))
    )
    (net (code "107") (name "~{A_CS}") (class "Default")
      (node (ref "ATMEGA328P") (pin "9") (pinfunction "PD5_9") (pintype "bidirectional"))
      (node (ref "U$7") (pin "9") (pinfunction "LOAD/CSN_9") (pintype "bidirectional"))
    )
    (net (code "108") (name "~{B_CS}") (class "Default")
      (node (ref "ATMEGA328P") (pin "2") (pinfunction "PD4_2") (pintype "bidirectional"))
      (node (ref "U$8") (pin "9") (pinfunction "LOAD/CSN_9") (pintype "bidirectional"))
    )
    (net (code "109") (name "~{CS_CAN}") (class "Default")
      (node (ref "ATMEGA328P") (pin "28") (pinfunction "PC5_28") (pintype "bidirectional"))
      (node (ref "U$2") (pin "16") (pinfunction "~{CS}_16") (pintype "input"))
    )
    (net (code "110") (name "~{C_CS}") (class "Default")
      (node (ref "ATMEGA328P") (pin "1") (pinfunction "PD3_1") (pintype "bidirectional"))
      (node (ref "U$9") (pin "9") (pinfunction "LOAD/CSN_9") (pintype "bidirectional"))
    )
    (net (code "111") (name "~{INT_CAN}") (class "Default")
      (node (ref "ATMEGA328P") (pin "32") (pinfunction "PD2_32") (pintype "bidirectional"))
      (node (ref "U$2") (pin "12") (pinfunction "~{INT}_12") (pintype "output"))
    )
  )
)
